# design.net
KiCad netlist of a schematic drawn in Altium Designer
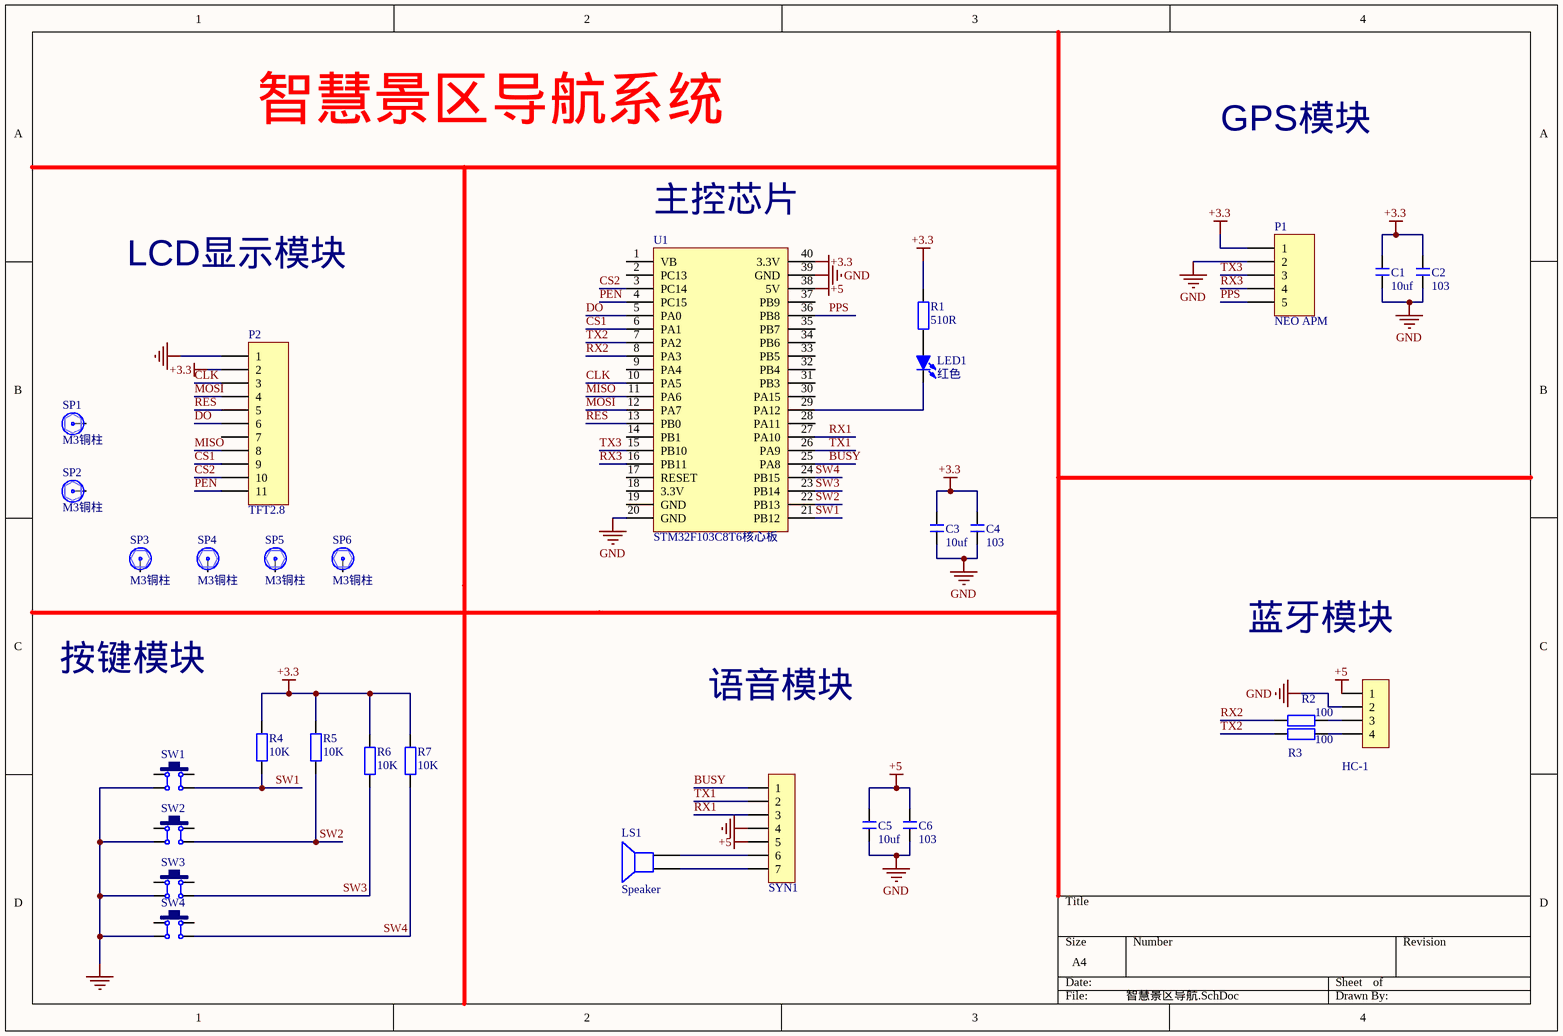
[diagram p0: 智慧景区导航.SchDoc]

(export (version "E")
  (design (tool "Eeschema 10.0.6"))
  (components
    (comp (ref "C1")
      (value "10uf")
      (footprint "R 0805_M")
      (description "直插瓷片电容")
      (fields (field (name "版权归属") "源创客"))
      (libsource (lib "3.1   - 电阻-电容-电感") (part "C-CC"))
    )
    (comp (ref "C2")
      (value "103")
      (footprint "R 0805_M")
      (description "直插瓷片电容")
      (fields (field (name "版权归属") "源创客"))
      (libsource (lib "3.1   - 电阻-电容-电感") (part "C-CC"))
    )
    (comp (ref "C3")
      (value "10uf")
      (footprint "R 0805_M")
      (description "直插瓷片电容")
      (fields (field (name "版权归属") "源创客"))
      (libsource (lib "3.1   - 电阻-电容-电感") (part "C-CC"))
    )
    (comp (ref "C4")
      (value "103")
      (footprint "R 0805_M")
      (description "直插瓷片电容")
      (fields (field (name "版权归属") "源创客"))
      (libsource (lib "3.1   - 电阻-电容-电感") (part "C-CC"))
    )
    (comp (ref "C5")
      (value "10uf")
      (footprint "R 0805_M")
      (description "直插瓷片电容")
      (fields (field (name "版权归属") "源创客"))
      (libsource (lib "3.1   - 电阻-电容-电感") (part "C-CC"))
    )
    (comp (ref "C6")
      (value "103")
      (footprint "R 0805_M")
      (description "直插瓷片电容")
      (fields (field (name "版权归属") "源创客"))
      (libsource (lib "3.1   - 电阻-电容-电感") (part "C-CC"))
    )
    (comp (ref "HC-1")
      (value "HDR-1X4")
      (footprint "HDR2.54-M-LI-4P")
      (description "4P接插件")
      (fields (field (name "版权归属") "源创客"))
      (libsource (lib "4.5   - 接插件-脚距2.54") (part "Header 4"))
    )
    (comp (ref "LED1")
      (value "红色")
      (footprint "LED 0805R")
      (description "贴片LED")
      (fields (field (name "版权归属") "源创客"))
      (libsource (lib "9.1   - LED") (part "LED-SMD"))
    )
    (comp (ref "LS1")
      (value "Speaker")
      (footprint "PIN2")
      (description "Loudspeaker")
      (fields (field (name "PUBLISHER") "Altium Limited"))
      (libsource (lib "Miscellaneous Devices") (part "Speaker"))
    )
    (comp (ref "P1")
      (value "NEO APM")
      (footprint "HDR1X5")
      (description "Header, 5-Pin")
      (fields (field (name "PUBLISHER") "Altium Limited"))
      (libsource (lib "Miscellaneous Connectors") (part "Header 5"))
    )
    (comp (ref "P2")
      (value "TFT2.8")
      (footprint "HDR1X11")
      (description "Header, 11-Pin")
      (fields (field (name "PUBLISHER") "Altium Limited"))
      (libsource (lib "Miscellaneous Connectors") (part "Header 11"))
    )
    (comp (ref "R1")
      (value "510R")
      (footprint "R 0805_M")
      (description "直插色环电阻")
      (fields (field (name "版权归属") "源创客"))
      (libsource (lib "3.1   - 电阻-电容-电感") (part "R-CRR"))
    )
    (comp (ref "R2")
      (value "100")
      (footprint "R 0805_M")
      (description "直插色环电阻")
      (fields (field (name "版权归属") "源创客"))
      (libsource (lib "3.1   - 电阻-电容-电感") (part "R-CRR"))
    )
    (comp (ref "R3")
      (value "100")
      (footprint "R 0805_M")
      (description "直插色环电阻")
      (fields (field (name "版权归属") "源创客"))
      (libsource (lib "3.1   - 电阻-电容-电感") (part "R-CRR"))
    )
    (comp (ref "R4")
      (value "10K")
      (footprint "R 0805_M")
      (description "直插色环电阻")
      (fields (field (name "版权归属") "源创客"))
      (libsource (lib "3.1   - 电阻-电容-电感") (part "R-CRR"))
    )
    (comp (ref "R5")
      (value "10K")
      (footprint "R 0805_M")
      (description "直插色环电阻")
      (fields (field (name "版权归属") "源创客"))
      (libsource (lib "3.1   - 电阻-电容-电感") (part "R-CRR"))
    )
    (comp (ref "R6")
      (value "10K")
      (footprint "R 0805_M")
      (description "直插色环电阻")
      (fields (field (name "版权归属") "源创客"))
      (libsource (lib "3.1   - 电阻-电容-电感") (part "R-CRR"))
    )
    (comp (ref "R7")
      (value "10K")
      (footprint "R 0805_M")
      (description "直插色环电阻")
      (fields (field (name "版权归属") "源创客"))
      (libsource (lib "3.1   - 电阻-电容-电感") (part "R-CRR"))
    )
    (comp (ref "SP1")
      (value "M3铜柱")
      (footprint "M3x4_L")
      (description "铜柱")
      (fields (field (name "版权归属") "源创客"))
      (libsource (lib "15.1 - 未分类器件") (part "铜柱小焊盘"))
    )
    (comp (ref "SP2")
      (value "M3铜柱")
      (footprint "M3x4_L")
      (description "铜柱")
      (fields (field (name "版权归属") "源创客"))
      (libsource (lib "15.1 - 未分类器件") (part "铜柱小焊盘"))
    )
    (comp (ref "SP3")
      (value "M3铜柱")
      (footprint "M3x4_L")
      (description "铜柱")
      (fields (field (name "版权归属") "源创客"))
      (libsource (lib "15.1 - 未分类器件") (part "铜柱小焊盘"))
    )
    (comp (ref "SP4")
      (value "M3铜柱")
      (footprint "M3x4_L")
      (description "铜柱")
      (fields (field (name "版权归属") "源创客"))
      (libsource (lib "15.1 - 未分类器件") (part "铜柱小焊盘"))
    )
    (comp (ref "SP5")
      (value "M3铜柱")
      (footprint "M3x4_L")
      (description "铜柱")
      (fields (field (name "版权归属") "源创客"))
      (libsource (lib "15.1 - 未分类器件") (part "铜柱小焊盘"))
    )
    (comp (ref "SP6")
      (value "M3铜柱")
      (footprint "M3x4_L")
      (description "铜柱")
      (fields (field (name "版权归属") "源创客"))
      (libsource (lib "15.1 - 未分类器件") (part "铜柱小焊盘"))
    )
    (comp (ref "SW1")
      (value "6x6x5")
      (footprint "TSW DIP-6*6*6")
      (description "直插6x6轻触开关")
      (libsource (lib "《源创客》元件符号库") (part "TSW DIP-6x6"))
    )
    (comp (ref "SW2")
      (value "6x6x5")
      (footprint "TSW DIP-6*6*6")
      (description "直插6x6轻触开关")
      (libsource (lib "《源创客》元件符号库") (part "TSW DIP-6x6"))
    )
    (comp (ref "SW3")
      (value "6x6x5")
      (footprint "TSW DIP-6*6*6")
      (description "直插6x6轻触开关")
      (libsource (lib "《源创客》元件符号库") (part "TSW DIP-6x6"))
    )
    (comp (ref "SW4")
      (value "6x6x5")
      (footprint "TSW DIP-6*6*6")
      (description "直插6x6轻触开关")
      (libsource (lib "《源创客》元件符号库") (part "TSW DIP-6x6"))
    )
    (comp (ref "SYN1")
      (value "HDR-1X7")
      (footprint "PH2.0-LI-7P")
      (description "7P接插件")
      (fields (field (name "版权归属") "源创客"))
      (libsource (lib "4.4   - 接插件-脚距2.0") (part "Header 7"))
    )
    (comp (ref "U1")
      (value "STM32F103C8T6核心板")
      (footprint "DIP40-600_MH")
      (libsource (lib "STM32F103C8T6核心板") (part "STM32F103C8T6核心板"))
    )
  )
  (nets
    (net (code "1") (name "+3.3") (class "Default")
      (node (ref "C1") (pin "1") (pinfunction "1_1") (pintype "passive"))
      (node (ref "C2") (pin "1") (pinfunction "1_1") (pintype "passive"))
      (node (ref "C3") (pin "1") (pinfunction "1_1") (pintype "passive"))
      (node (ref "C4") (pin "1") (pinfunction "1_1") (pintype "passive"))
      (node (ref "P1") (pin "1") (pinfunction "1_1") (pintype "passive"))
      (node (ref "P2") (pin "2") (pinfunction "2_2") (pintype "passive"))
      (node (ref "R1") (pin "2") (pinfunction "2_2") (pintype "passive"))
      (node (ref "R4") (pin "2") (pinfunction "2_2") (pintype "passive"))
      (node (ref "R5") (pin "2") (pinfunction "2_2") (pintype "passive"))
      (node (ref "R6") (pin "2") (pinfunction "2_2") (pintype "passive"))
      (node (ref "R7") (pin "2") (pinfunction "2_2") (pintype "passive"))
      (node (ref "U1") (pin "40") (pinfunction "3.3V_40") (pintype "passive"))
    )
    (net (code "2") (name "+5") (class "Default")
      (node (ref "C5") (pin "1") (pinfunction "1_1") (pintype "passive"))
      (node (ref "C6") (pin "1") (pinfunction "1_1") (pintype "passive"))
      (node (ref "HC-1") (pin "1") (pinfunction "1_1") (pintype "passive"))
      (node (ref "SYN1") (pin "5") (pinfunction "5_5") (pintype "passive"))
      (node (ref "U1") (pin "38") (pinfunction "5V_38") (pintype "passive"))
    )
    (net (code "3") (name "/BUSY") (class "Default")
      (node (ref "SYN1") (pin "1") (pinfunction "1_1") (pintype "passive"))
      (node (ref "U1") (pin "25") (pinfunction "PA8_25") (pintype "passive"))
    )
    (net (code "4") (name "/CLK") (class "Default")
      (node (ref "P2") (pin "3") (pinfunction "3_3") (pintype "passive"))
      (node (ref "U1") (pin "10") (pinfunction "PA5_10") (pintype "passive"))
    )
    (net (code "5") (name "/CS1") (class "Default")
      (node (ref "P2") (pin "9") (pinfunction "9_9") (pintype "passive"))
      (node (ref "U1") (pin "6") (pinfunction "PA1_6") (pintype "passive"))
    )
    (net (code "6") (name "/CS2") (class "Default")
      (node (ref "P2") (pin "10") (pinfunction "10_10") (pintype "passive"))
      (node (ref "U1") (pin "3") (pinfunction "PC14_3") (pintype "passive"))
    )
    (net (code "7") (name "/DO") (class "Default")
      (node (ref "P2") (pin "6") (pinfunction "6_6") (pintype "passive"))
      (node (ref "U1") (pin "5") (pinfunction "PA0_5") (pintype "passive"))
    )
    (net (code "8") (name "/MISO") (class "Default")
      (node (ref "P2") (pin "8") (pinfunction "8_8") (pintype "passive"))
      (node (ref "U1") (pin "11") (pinfunction "PA6_11") (pintype "passive"))
    )
    (net (code "9") (name "/MOSI") (class "Default")
      (node (ref "P2") (pin "4") (pinfunction "4_4") (pintype "passive"))
      (node (ref "U1") (pin "12") (pinfunction "PA7_12") (pintype "passive"))
    )
    (net (code "10") (name "/PEN") (class "Default")
      (node (ref "P2") (pin "11") (pinfunction "11_11") (pintype "passive"))
      (node (ref "U1") (pin "4") (pinfunction "PC15_4") (pintype "passive"))
    )
    (net (code "11") (name "/PPS") (class "Default")
      (node (ref "P1") (pin "5") (pinfunction "5_5") (pintype "passive"))
      (node (ref "U1") (pin "36") (pinfunction "PB8_36") (pintype "passive"))
    )
    (net (code "12") (name "/RES") (class "Default")
      (node (ref "P2") (pin "5") (pinfunction "5_5") (pintype "passive"))
      (node (ref "U1") (pin "13") (pinfunction "PB0_13") (pintype "passive"))
    )
    (net (code "13") (name "/RX1") (class "Default")
      (node (ref "SYN1") (pin "3") (pinfunction "3_3") (pintype "passive"))
      (node (ref "U1") (pin "27") (pinfunction "PA10_27") (pintype "passive"))
    )
    (net (code "14") (name "/RX2") (class "Default")
      (node (ref "R2") (pin "2") (pinfunction "2_2") (pintype "passive"))
      (node (ref "U1") (pin "8") (pinfunction "PA3_8") (pintype "passive"))
    )
    (net (code "15") (name "/RX3") (class "Default")
      (node (ref "P1") (pin "4") (pinfunction "4_4") (pintype "passive"))
      (node (ref "U1") (pin "16") (pinfunction "PB11_16") (pintype "passive"))
    )
    (net (code "16") (name "/SW1") (class "Default")
      (node (ref "R4") (pin "1") (pinfunction "1_1") (pintype "passive"))
      (node (ref "SW1") (pin "4") (pinfunction "4_4") (pintype "passive"))
      (node (ref "U1") (pin "21") (pinfunction "PB12_21") (pintype "passive"))
    )
    (net (code "17") (name "/SW2") (class "Default")
      (node (ref "R5") (pin "1") (pinfunction "1_1") (pintype "passive"))
      (node (ref "SW2") (pin "4") (pinfunction "4_4") (pintype "passive"))
      (node (ref "U1") (pin "22") (pinfunction "PB13_22") (pintype "passive"))
    )
    (net (code "18") (name "/SW3") (class "Default")
      (node (ref "R6") (pin "1") (pinfunction "1_1") (pintype "passive"))
      (node (ref "SW3") (pin "4") (pinfunction "4_4") (pintype "passive"))
      (node (ref "U1") (pin "23") (pinfunction "PB14_23") (pintype "passive"))
    )
    (net (code "19") (name "/SW4") (class "Default")
      (node (ref "R7") (pin "1") (pinfunction "1_1") (pintype "passive"))
      (node (ref "SW4") (pin "4") (pinfunction "4_4") (pintype "passive"))
      (node (ref "U1") (pin "24") (pinfunction "PB15_24") (pintype "passive"))
    )
    (net (code "20") (name "/TX1") (class "Default")
      (node (ref "SYN1") (pin "2") (pinfunction "2_2") (pintype "passive"))
      (node (ref "U1") (pin "26") (pinfunction "PA9_26") (pintype "passive"))
    )
    (net (code "21") (name "/TX2") (class "Default")
      (node (ref "R3") (pin "2") (pinfunction "2_2") (pintype "passive"))
      (node (ref "U1") (pin "7") (pinfunction "PA2_7") (pintype "passive"))
    )
    (net (code "22") (name "/TX3") (class "Default")
      (node (ref "P1") (pin "3") (pinfunction "3_3") (pintype "passive"))
      (node (ref "U1") (pin "15") (pinfunction "PB10_15") (pintype "passive"))
    )
    (net (code "23") (name "GND") (class "Default")
      (node (ref "C1") (pin "2") (pinfunction "2_2") (pintype "passive"))
      (node (ref "C2") (pin "2") (pinfunction "2_2") (pintype "passive"))
      (node (ref "C3") (pin "2") (pinfunction "2_2") (pintype "passive"))
      (node (ref "C4") (pin "2") (pinfunction "2_2") (pintype "passive"))
      (node (ref "C5") (pin "2") (pinfunction "2_2") (pintype "passive"))
      (node (ref "C6") (pin "2") (pinfunction "2_2") (pintype "passive"))
      (node (ref "HC-1") (pin "2") (pinfunction "2_2") (pintype "passive"))
      (node (ref "P1") (pin "2") (pinfunction "2_2") (pintype "passive"))
      (node (ref "P2") (pin "1") (pinfunction "1_1") (pintype "passive"))
      (node (ref "SW1") (pin "2") (pinfunction "2_2") (pintype "passive"))
      (node (ref "SW2") (pin "2") (pinfunction "2_2") (pintype "passive"))
      (node (ref "SW3") (pin "2") (pinfunction "2_2") (pintype "passive"))
      (node (ref "SW4") (pin "2") (pinfunction "2_2") (pintype "passive"))
      (node (ref "SYN1") (pin "4") (pinfunction "4_4") (pintype "passive"))
      (node (ref "U1") (pin "20") (pinfunction "GND_20") (pintype "passive"))
      (node (ref "U1") (pin "39") (pinfunction "GND_39") (pintype "passive"))
    )
    (net (code "24") (name "Net-(HC-1-Pad3)") (class "Default")
      (node (ref "HC-1") (pin "3") (pinfunction "3_3") (pintype "passive"))
      (node (ref "R2") (pin "1") (pinfunction "1_1") (pintype "passive"))
    )
    (net (code "25") (name "Net-(HC-1-Pad4)") (class "Default")
      (node (ref "HC-1") (pin "4") (pinfunction "4_4") (pintype "passive"))
      (node (ref "R3") (pin "1") (pinfunction "1_1") (pintype "passive"))
    )
    (net (code "26") (name "Net-(LED1-A)") (class "Default")
      (node (ref "LED1") (pin "1") (pinfunction "A_1") (pintype "passive"))
      (node (ref "R1") (pin "1") (pinfunction "1_1") (pintype "passive"))
    )
    (net (code "27") (name "Net-(LED1-K)") (class "Default")
      (node (ref "LED1") (pin "2") (pinfunction "K_2") (pintype "passive"))
      (node (ref "U1") (pin "29") (pinfunction "PA12_29") (pintype "passive"))
    )
    (net (code "28") (name "Net-(LS1-Pad1)") (class "Default")
      (node (ref "LS1") (pin "1") (pinfunction "1_1") (pintype "passive"))
      (node (ref "SYN1") (pin "7") (pinfunction "7_7") (pintype "passive"))
    )
    (net (code "29") (name "Net-(LS1-Pad2)") (class "Default")
      (node (ref "LS1") (pin "2") (pinfunction "2_2") (pintype "passive"))
      (node (ref "SYN1") (pin "6") (pinfunction "6_6") (pintype "passive"))
    )
    (net (code "30") (name "unconnected-(P2-Pad7)") (class "Default")
      (node (ref "P2") (pin "7") (pinfunction "7_7") (pintype "passive"))
    )
    (net (code "31") (name "unconnected-(SP1-Pad1)") (class "Default")
      (node (ref "SP1") (pin "1") (pinfunction "1_1") (pintype "passive"))
    )
    (net (code "32") (name "unconnected-(SP2-Pad1)") (class "Default")
      (node (ref "SP2") (pin "1") (pinfunction "1_1") (pintype "passive"))
    )
    (net (code "33") (name "unconnected-(SP3-Pad1)") (class "Default")
      (node (ref "SP3") (pin "1") (pinfunction "1_1") (pintype "passive"))
    )
    (net (code "34") (name "unconnected-(SP4-Pad1)") (class "Default")
      (node (ref "SP4") (pin "1") (pinfunction "1_1") (pintype "passive"))
    )
    (net (code "35") (name "unconnected-(SP5-Pad1)") (class "Default")
      (node (ref "SP5") (pin "1") (pinfunction "1_1") (pintype "passive"))
    )
    (net (code "36") (name "unconnected-(SP6-Pad1)") (class "Default")
      (node (ref "SP6") (pin "1") (pinfunction "1_1") (pintype "passive"))
    )
    (net (code "37") (name "unconnected-(SW1-2-Pad3)") (class "Default")
      (node (ref "SW1") (pin "3") (pinfunction "2_3") (pintype "passive"))
    )
    (net (code "38") (name "unconnected-(SW1-Pad1)") (class "Default")
      (node (ref "SW1") (pin "1") (pinfunction "1_1") (pintype "passive"))
    )
    (net (code "39") (name "unconnected-(SW2-2-Pad3)") (class "Default")
      (node (ref "SW2") (pin "3") (pinfunction "2_3") (pintype "passive"))
    )
    (net (code "40") (name "unconnected-(SW2-Pad1)") (class "Default")
      (node (ref "SW2") (pin "1") (pinfunction "1_1") (pintype "passive"))
    )
    (net (code "41") (name "unconnected-(SW3-2-Pad3)") (class "Default")
      (node (ref "SW3") (pin "3") (pinfunction "2_3") (pintype "passive"))
    )
    (net (code "42") (name "unconnected-(SW3-Pad1)") (class "Default")
      (node (ref "SW3") (pin "1") (pinfunction "1_1") (pintype "passive"))
    )
    (net (code "43") (name "unconnected-(SW4-2-Pad3)") (class "Default")
      (node (ref "SW4") (pin "3") (pinfunction "2_3") (pintype "passive"))
    )
    (net (code "44") (name "unconnected-(SW4-Pad1)") (class "Default")
      (node (ref "SW4") (pin "1") (pinfunction "1_1") (pintype "passive"))
    )
    (net (code "45") (name "unconnected-(U1-3.3V-Pad18)") (class "Default")
      (node (ref "U1") (pin "18") (pinfunction "3.3V_18") (pintype "passive"))
    )
    (net (code "46") (name "unconnected-(U1-GND-Pad19)") (class "Default")
      (node (ref "U1") (pin "19") (pinfunction "GND_19") (pintype "passive"))
    )
    (net (code "47") (name "unconnected-(U1-PA4-Pad9)") (class "Default")
      (node (ref "U1") (pin "9") (pinfunction "PA4_9") (pintype "passive"))
    )
    (net (code "48") (name "unconnected-(U1-PA11-Pad28)") (class "Default")
      (node (ref "U1") (pin "28") (pinfunction "PA11_28") (pintype "passive"))
    )
    (net (code "49") (name "unconnected-(U1-PA15-Pad30)") (class "Default")
      (node (ref "U1") (pin "30") (pinfunction "PA15_30") (pintype "passive"))
    )
    (net (code "50") (name "unconnected-(U1-PB1-Pad14)") (class "Default")
      (node (ref "U1") (pin "14") (pinfunction "PB1_14") (pintype "passive"))
    )
    (net (code "51") (name "unconnected-(U1-PB3-Pad31)") (class "Default")
      (node (ref "U1") (pin "31") (pinfunction "PB3_31") (pintype "passive"))
    )
    (net (code "52") (name "unconnected-(U1-PB4-Pad32)") (class "Default")
      (node (ref "U1") (pin "32") (pinfunction "PB4_32") (pintype "passive"))
    )
    (net (code "53") (name "unconnected-(U1-PB5-Pad33)") (class "Default")
      (node (ref "U1") (pin "33") (pinfunction "PB5_33") (pintype "passive"))
    )
    (net (code "54") (name "unconnected-(U1-PB6-Pad34)") (class "Default")
      (node (ref "U1") (pin "34") (pinfunction "PB6_34") (pintype "passive"))
    )
    (net (code "55") (name "unconnected-(U1-PB7-Pad35)") (class "Default")
      (node (ref "U1") (pin "35") (pinfunction "PB7_35") (pintype "passive"))
    )
    (net (code "56") (name "unconnected-(U1-PB9-Pad37)") (class "Default")
      (node (ref "U1") (pin "37") (pinfunction "PB9_37") (pintype "passive"))
    )
    (net (code "57") (name "unconnected-(U1-PC13-Pad2)") (class "Default")
      (node (ref "U1") (pin "2") (pinfunction "PC13_2") (pintype "passive"))
    )
    (net (code "58") (name "unconnected-(U1-RESET-Pad17)") (class "Default")
      (node (ref "U1") (pin "17") (pinfunction "RESET_17") (pintype "passive"))
    )
    (net (code "59") (name "unconnected-(U1-VB-Pad1)") (class "Default")
      (node (ref "U1") (pin "1") (pinfunction "VB_1") (pintype "passive"))
    )
  )
)
